# watch_v1_test_Rev01.net
KiCad netlist of a schematic drawn in EAGLE
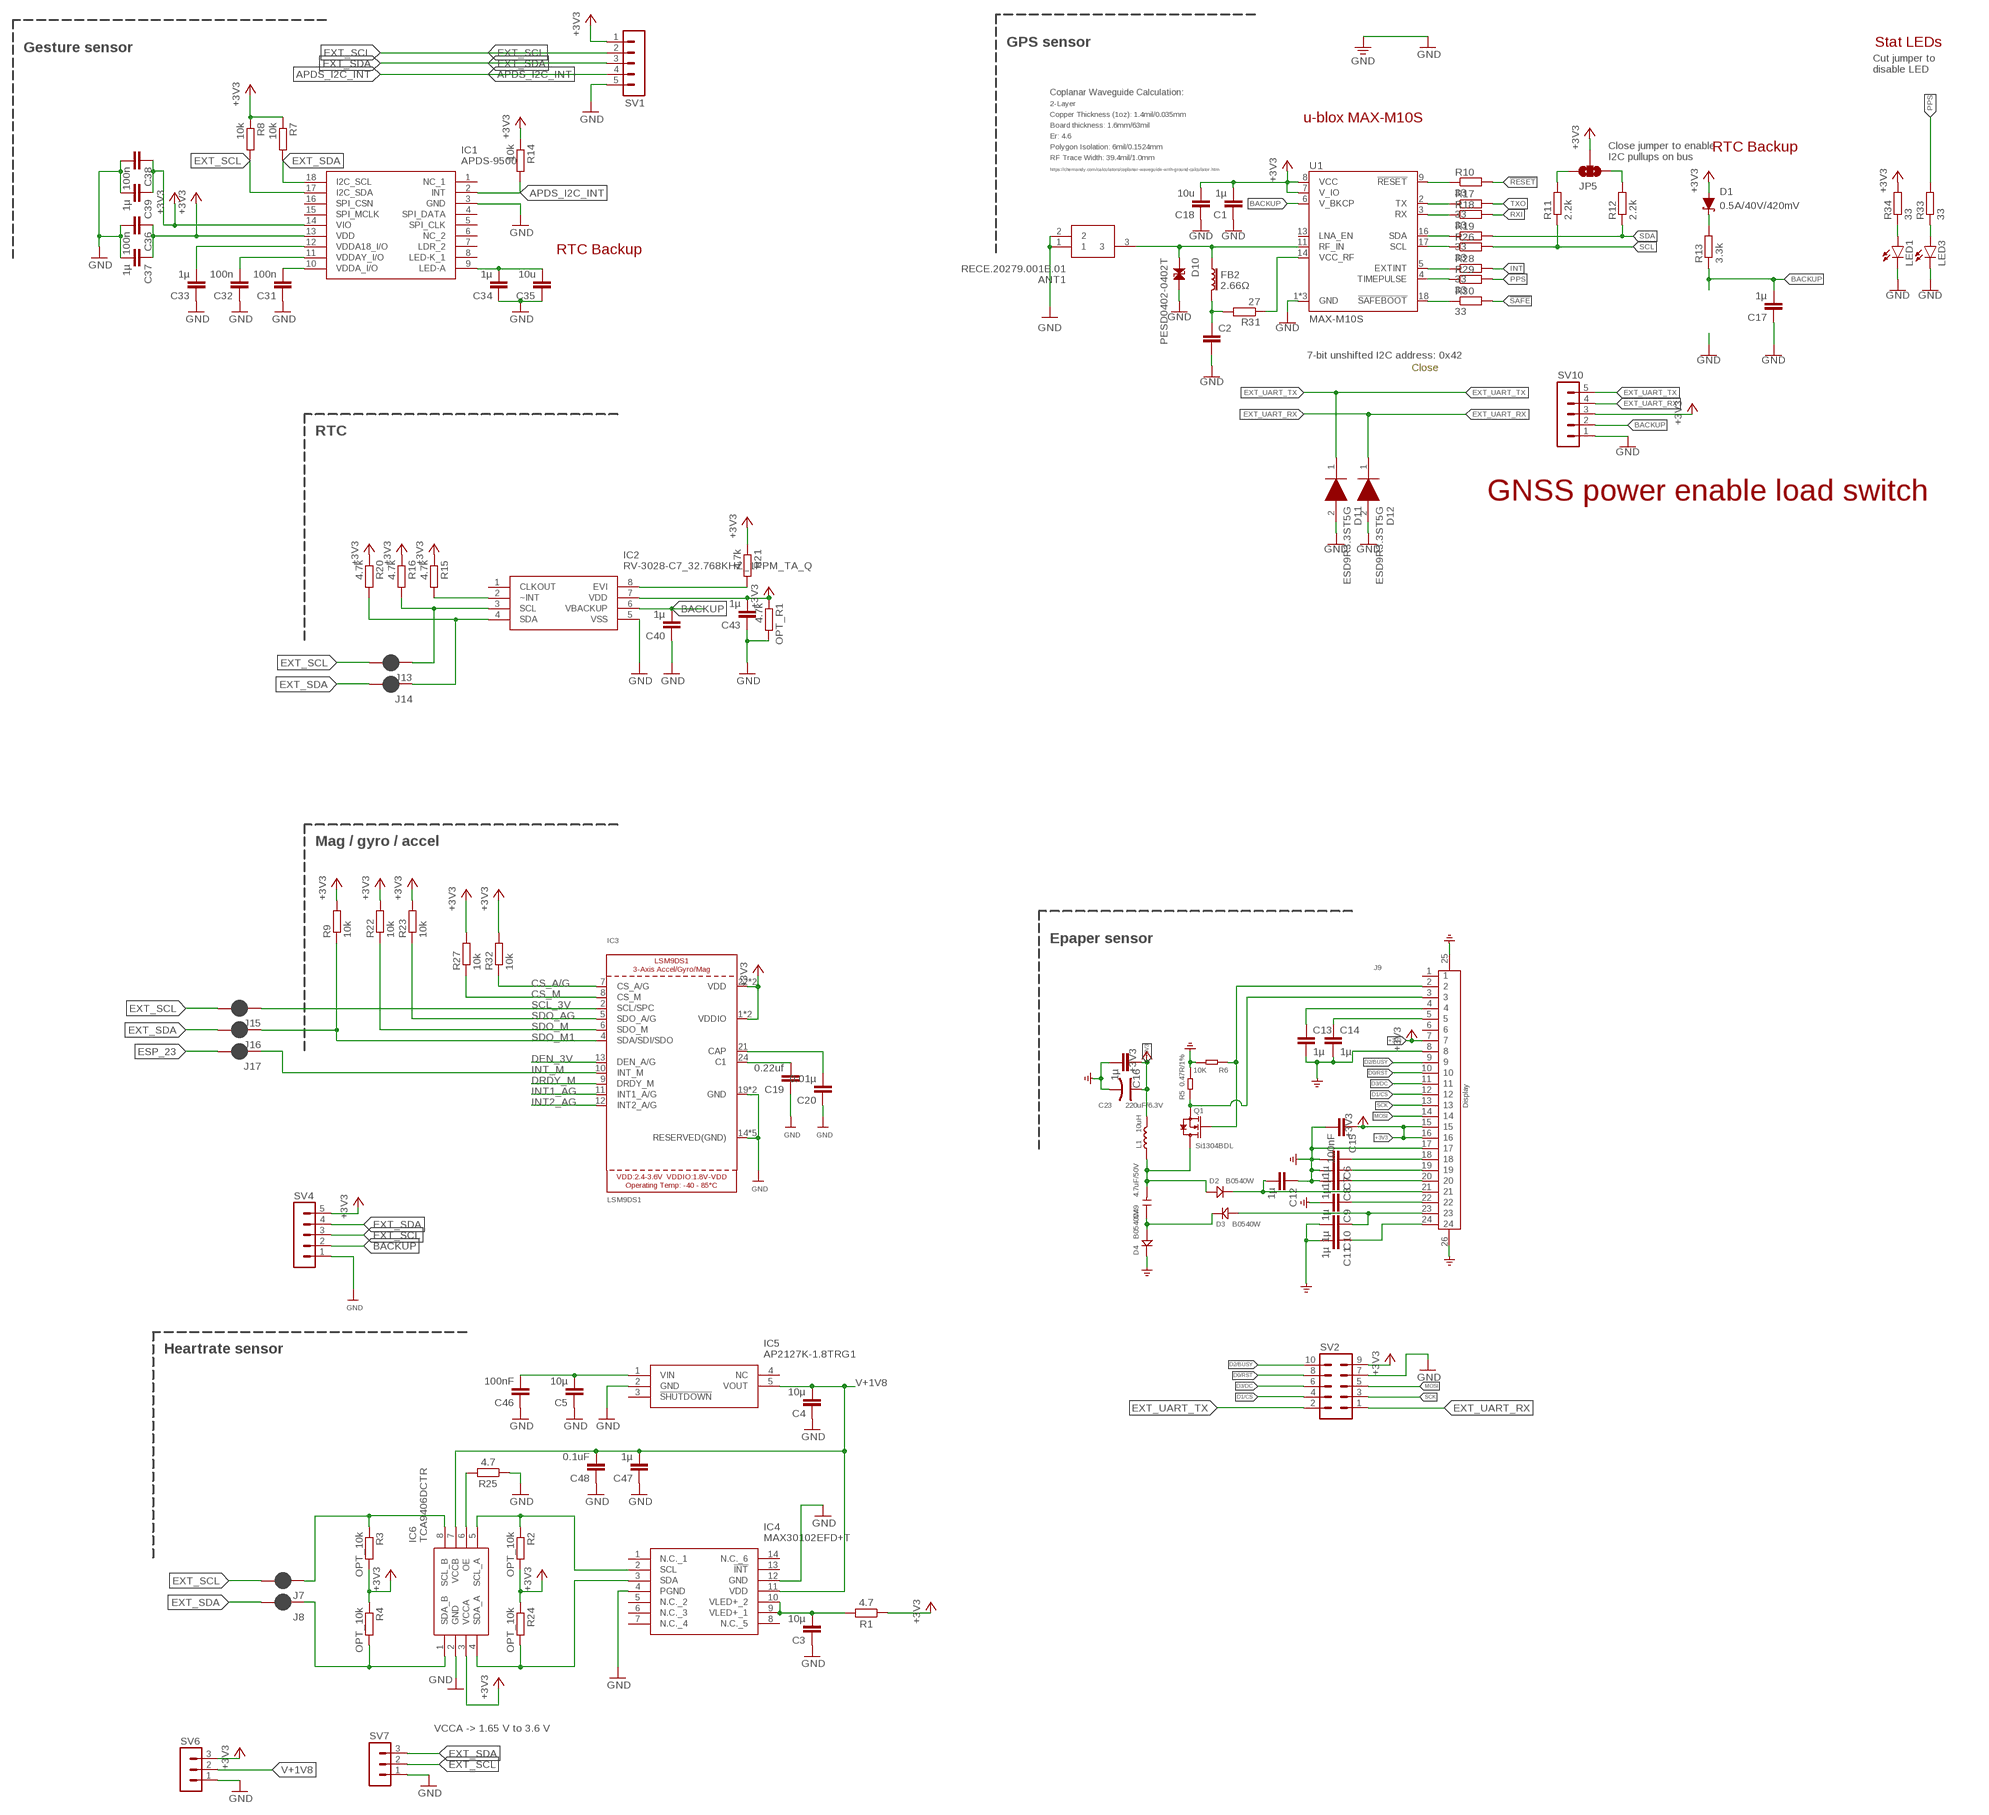
[diagram p0: schematic, sheet 1]

(export (version "E")
  (design (tool "Eeschema 10.0.6"))
  (components
    (comp (ref "ANT1")
      (value "RECE.20279.001E.01")
      (footprint "eagle-import:RECE.20279.001E.01")
      (fields (field (name "MOUSER_PART_NUMBER") "960-RECE20279001E01"))
      (libsource (lib "eagle-import") (part "RECE.20279.001E.01"))
    )
    (comp (ref "C1")
      (value "1µ")
      (footprint "eagle-import:C0402_S")
      (libsource (lib "eagle-import") (part "C0402_S"))
    )
    (comp (ref "C2")
      (value "47pF")
      (footprint "eagle-import:0402-TIGHT")
      (libsource (lib "eagle-import") (part "47PF-0402_TIGHT-25V-5%-X7R"))
    )
    (comp (ref "C3")
      (value "10µ")
      (footprint "eagle-import:C0402_S")
      (libsource (lib "eagle-import") (part "C0402_S"))
    )
    (comp (ref "C4")
      (value "10µ")
      (footprint "eagle-import:C0402_S")
      (libsource (lib "eagle-import") (part "C0402_S"))
    )
    (comp (ref "C5")
      (value "10µ")
      (footprint "eagle-import:C0402_S")
      (libsource (lib "eagle-import") (part "C0402_S"))
    )
    (comp (ref "C6")
      (value "1µ")
      (footprint "eagle-import:C0402_S")
      (libsource (lib "eagle-import") (part "C0402_S"))
    )
    (comp (ref "C7")
      (value "1µ")
      (footprint "eagle-import:C0402_S")
      (libsource (lib "eagle-import") (part "C0402_S"))
    )
    (comp (ref "C8")
      (value "1µ")
      (footprint "eagle-import:C0402_S")
      (libsource (lib "eagle-import") (part "C0402_S"))
    )
    (comp (ref "C9")
      (value "1µ")
      (footprint "eagle-import:C0402_S")
      (libsource (lib "eagle-import") (part "C0402_S"))
    )
    (comp (ref "C10")
      (value "1µ")
      (footprint "eagle-import:C0402_S")
      (libsource (lib "eagle-import") (part "C0402_S"))
    )
    (comp (ref "C11")
      (value "1µ")
      (footprint "eagle-import:C0402_S")
      (libsource (lib "eagle-import") (part "C0402_S"))
    )
    (comp (ref "C12")
      (value "1µ")
      (footprint "eagle-import:C0402_S")
      (libsource (lib "eagle-import") (part "C0402_S"))
    )
    (comp (ref "C13")
      (value "1µ")
      (footprint "eagle-import:C0402_S")
      (libsource (lib "eagle-import") (part "C0402_S"))
    )
    (comp (ref "C14")
      (value "1µ")
      (footprint "eagle-import:C0402_S")
      (libsource (lib "eagle-import") (part "C0402_S"))
    )
    (comp (ref "C15")
      (value "100nF")
      (footprint "eagle-import:C0402_S")
      (libsource (lib "eagle-import") (part "C0402_S"))
    )
    (comp (ref "C16")
      (value "1µ")
      (footprint "eagle-import:C0402_S")
      (libsource (lib "eagle-import") (part "C0402_S"))
    )
    (comp (ref "C17")
      (value "1µ")
      (footprint "eagle-import:C0402_S")
      (libsource (lib "eagle-import") (part "C0402_S"))
    )
    (comp (ref "C18")
      (value "10u")
      (footprint "eagle-import:C0402_S")
      (libsource (lib "eagle-import") (part "C0402_S"))
    )
    (comp (ref "C19")
      (value "0.22uf")
      (footprint "eagle-import:C0402_S")
      (libsource (lib "eagle-import") (part "C0402_S"))
    )
    (comp (ref "C20")
      (value "0.01µ")
      (footprint "eagle-import:C0402_S")
      (libsource (lib "eagle-import") (part "C0402_S"))
    )
    (comp (ref "C23")
      (value "220uF/6.3V")
      (footprint "eagle-import:AVX-B")
      (libsource (lib "eagle-import") (part "CAP-POLAR-AVX-B"))
    )
    (comp (ref "C31")
      (value "100n")
      (footprint "eagle-import:C0402_S")
      (libsource (lib "eagle-import") (part "C0402_S"))
    )
    (comp (ref "C32")
      (value "100n")
      (footprint "eagle-import:C0402_S")
      (libsource (lib "eagle-import") (part "C0402_S"))
    )
    (comp (ref "C33")
      (value "1µ")
      (footprint "eagle-import:C0402_S")
      (libsource (lib "eagle-import") (part "C0402_S"))
    )
    (comp (ref "C34")
      (value "1µ")
      (footprint "eagle-import:C0402_S")
      (libsource (lib "eagle-import") (part "C0402_S"))
    )
    (comp (ref "C35")
      (value "10u")
      (footprint "eagle-import:C0402_S")
      (libsource (lib "eagle-import") (part "C0402_S"))
    )
    (comp (ref "C36")
      (value "100n")
      (footprint "eagle-import:C0402_S")
      (libsource (lib "eagle-import") (part "C0402_S"))
    )
    (comp (ref "C37")
      (value "1µ")
      (footprint "eagle-import:C0402_S")
      (libsource (lib "eagle-import") (part "C0402_S"))
    )
    (comp (ref "C38")
      (value "100n")
      (footprint "eagle-import:C0402_S")
      (libsource (lib "eagle-import") (part "C0402_S"))
    )
    (comp (ref "C39")
      (value "1µ")
      (footprint "eagle-import:C0402_S")
      (libsource (lib "eagle-import") (part "C0402_S"))
    )
    (comp (ref "C40")
      (value "1µ")
      (footprint "eagle-import:C0402_S")
      (libsource (lib "eagle-import") (part "C0402_S"))
    )
    (comp (ref "C43")
      (value "1µ")
      (footprint "eagle-import:C0402_S")
      (libsource (lib "eagle-import") (part "C0402_S"))
    )
    (comp (ref "C46")
      (value "100nF")
      (footprint "eagle-import:C0402_S")
      (libsource (lib "eagle-import") (part "C0402_S"))
    )
    (comp (ref "C47")
      (value "1µ")
      (footprint "eagle-import:C0402_S")
      (libsource (lib "eagle-import") (part "C0402_S"))
    )
    (comp (ref "C48")
      (value "0.1uF")
      (footprint "eagle-import:C0402_S")
      (libsource (lib "eagle-import") (part "C0402_S"))
    )
    (comp (ref "C49")
      (value "4.7uF/50V")
      (footprint "eagle-import:C1206")
      (libsource (lib "eagle-import") (part "CAP-1206"))
    )
    (comp (ref "D1")
      (value "0.5A/40V/420mV")
      (footprint "eagle-import:SOD-323")
      (libsource (lib "eagle-import") (part "DIODE-SCHOTTKY-PMEG4005EJ"))
    )
    (comp (ref "D2")
      (value "B0540W")
      (footprint "eagle-import:SOD-323")
      (libsource (lib "eagle-import") (part "DIODE'0805'"))
    )
    (comp (ref "D3")
      (value "B0540W")
      (footprint "eagle-import:SOD-323")
      (libsource (lib "eagle-import") (part "DIODE'0805'"))
    )
    (comp (ref "D4")
      (value "B0540W")
      (footprint "eagle-import:SOD-323")
      (libsource (lib "eagle-import") (part "DIODE'0805'"))
    )
    (comp (ref "D10")
      (value "PESD0402-0402T")
      (footprint "eagle-import:0402-TIGHT")
      (libsource (lib "eagle-import") (part "PESD0402-0402T"))
    )
    (comp (ref "D11")
      (value "ESD9R3.3ST5G")
      (footprint "eagle-import:SODFL1006X40N")
      (fields (field (name "MOUSER_PART_NUMBER") "863-ESD9R3.3ST5G"))
      (libsource (lib "eagle-import") (part "ESD9R3.3ST5G"))
    )
    (comp (ref "D12")
      (value "ESD9R3.3ST5G")
      (footprint "eagle-import:SODFL1006X40N")
      (fields (field (name "MOUSER_PART_NUMBER") "863-ESD9R3.3ST5G"))
      (libsource (lib "eagle-import") (part "ESD9R3.3ST5G"))
    )
    (comp (ref "FB2")
      (value "2.66Ω")
      (footprint "eagle-import:0402-TIGHT")
      (libsource (lib "eagle-import") (part "FERRITE_BEAD-0402-2.66Ω-1GHZ"))
    )
    (comp (ref "IC1")
      (value "APDS-9500")
      (footprint "eagle-import:APDS9500")
      (fields (field (name "MOUSER_PART_NUMBER") "630-APDS-9500"))
      (libsource (lib "eagle-import") (part "APDS-9500"))
    )
    (comp (ref "IC2")
      (value "RV-3028-C7_32.768KHZ_1PPM_TA_Q")
      (footprint "eagle-import:RV3028C732768KHZ1PPMTAQC")
      (fields
        (field (name "MANUFACTURER_PART_NUMBER") "RV-3028-C7 32.768kHz 1ppm TA QC")
        (field (name "MOUSER_PART_NUMBER") "428-203591-MG01")
      )
      (libsource (lib "eagle-import") (part "RV-3028-C7_32.768KHZ_1PPM_TA_Q"))
    )
    (comp (ref "IC3")
      (value "LSM9DS1")
      (footprint "eagle-import:LGA24_3.5X3.1MM")
      (libsource (lib "eagle-import") (part "LSM9DS1"))
    )
    (comp (ref "IC4")
      (value "MAX30102EFD+T")
      (footprint "eagle-import:MAX30102EFDT")
      (fields (field (name "MOUSER_PART_NUMBER") "700-MAX30102EFD+T"))
      (libsource (lib "eagle-import") (part "MAX30102EFD+T"))
    )
    (comp (ref "IC5")
      (value "AP2127K-1.8TRG1")
      (footprint "eagle-import:SOT95P282X145-5N")
      (fields (field (name "MOUSER_PART_NUMBER") "621-AP2127K-1.8TRG1"))
      (libsource (lib "eagle-import") (part "AP2127K-1.8TRG1"))
    )
    (comp (ref "IC6")
      (value "TCA9406DCTR")
      (footprint "eagle-import:SOP65P400X130-8N")
      (fields (field (name "MOUSER_PART_NUMBER") "595-TCA9406DCTR"))
      (libsource (lib "eagle-import") (part "TCA9406DCTR"))
    )
    (comp (ref "J7")
      (value "SMT_JUMPER_2_NC_PASTE")
      (footprint "eagle-import:JUMPER_SMALL")
      (libsource (lib "eagle-import") (part "SMT_JUMPER_2_NC_PASTE"))
    )
    (comp (ref "J8")
      (value "SMT_JUMPER_2_NC_PASTE")
      (footprint "eagle-import:JUMPER_SMALL")
      (libsource (lib "eagle-import") (part "SMT_JUMPER_2_NC_PASTE"))
    )
    (comp (ref "J9")
      (value "Display")
      (footprint "eagle-import:FPCB24-SMD-0.5-17.6X5.0X2MM")
      (libsource (lib "eagle-import") (part "FPC-CONNECTOR-24P"))
    )
    (comp (ref "J13")
      (value "SMT_JUMPER_2_NC_PASTE")
      (footprint "eagle-import:JUMPER_SMALL")
      (libsource (lib "eagle-import") (part "SMT_JUMPER_2_NC_PASTE"))
    )
    (comp (ref "J14")
      (value "SMT_JUMPER_2_NC_PASTE")
      (footprint "eagle-import:JUMPER_SMALL")
      (libsource (lib "eagle-import") (part "SMT_JUMPER_2_NC_PASTE"))
    )
    (comp (ref "J15")
      (value "SMT_JUMPER_2_NC_PASTE")
      (footprint "eagle-import:JUMPER_SMALL")
      (libsource (lib "eagle-import") (part "SMT_JUMPER_2_NC_PASTE"))
    )
    (comp (ref "J16")
      (value "SMT_JUMPER_2_NC_PASTE")
      (footprint "eagle-import:JUMPER_SMALL")
      (libsource (lib "eagle-import") (part "SMT_JUMPER_2_NC_PASTE"))
    )
    (comp (ref "J17")
      (value "SMT_JUMPER_2_NC_PASTE")
      (footprint "eagle-import:JUMPER_SMALL")
      (libsource (lib "eagle-import") (part "SMT_JUMPER_2_NC_PASTE"))
    )
    (comp (ref "JP5")
      (value "JUMPER-SMT_3_NO_SILK")
      (footprint "eagle-import:SMT-JUMPER_3_NO_SILK")
      (libsource (lib "eagle-import") (part "JUMPER-SMT_3_NO_SILK"))
    )
    (comp (ref "L1")
      (value "10uH")
      (footprint "eagle-import:L0420")
      (libsource (lib "eagle-import") (part "INDUCTOR-SPD3D16-4R7M"))
    )
    (comp (ref "LED1")
      (value "LEDSML0603")
      (footprint "eagle-import:SML0603")
      (fields (field (name "MANUFACTURER") "Wurth Elektronik") (field (name "MPN") "150060GS84000"))
      (libsource (lib "eagle-import") (part "LEDSML0603"))
    )
    (comp (ref "LED3")
      (value "LEDSML0603")
      (footprint "eagle-import:SML0603")
      (fields (field (name "MANUFACTURER") "Wurth Elektronik") (field (name "MPN") "150060GS84000"))
      (libsource (lib "eagle-import") (part "LEDSML0603"))
    )
    (comp (ref "OPT_R1")
      (value "4.7k")
      (footprint "eagle-import:R0402")
      (libsource (lib "eagle-import") (part "R0402"))
    )
    (comp (ref "Q1")
      (value "Si1304BDL")
      (footprint "eagle-import:SOT-323")
      (libsource (lib "eagle-import") (part "MOSFET-N'SI1304BDL'"))
    )
    (comp (ref "R1")
      (value "4.7")
      (footprint "eagle-import:RESC1608X60")
      (libsource (lib "eagle-import") (part "RCHIP-0603(1608-METRIC)_"))
    )
    (comp (ref "R2")
      (value "OPT_10k")
      (footprint "eagle-import:R0402")
      (libsource (lib "eagle-import") (part "R0402"))
    )
    (comp (ref "R3")
      (value "OPT_10k")
      (footprint "eagle-import:R0402")
      (libsource (lib "eagle-import") (part "R0402"))
    )
    (comp (ref "R4")
      (value "OPT_10k")
      (footprint "eagle-import:R0402")
      (libsource (lib "eagle-import") (part "R0402"))
    )
    (comp (ref "R5")
      (value "0.47R/1%")
      (footprint "eagle-import:R0603")
      (libsource (lib "eagle-import") (part "RES-0603"))
    )
    (comp (ref "R6")
      (value "10K")
      (footprint "eagle-import:R0603")
      (libsource (lib "eagle-import") (part "RES-0603"))
    )
    (comp (ref "R7")
      (value "10k")
      (footprint "eagle-import:R0402")
      (libsource (lib "eagle-import") (part "R0402"))
    )
    (comp (ref "R8")
      (value "10k")
      (footprint "eagle-import:R0402")
      (libsource (lib "eagle-import") (part "R0402"))
    )
    (comp (ref "R9")
      (value "10k")
      (footprint "eagle-import:R0402")
      (libsource (lib "eagle-import") (part "R0402"))
    )
    (comp (ref "R10")
      (value "33")
      (footprint "eagle-import:R0402")
      (libsource (lib "eagle-import") (part "R0402"))
    )
    (comp (ref "R11")
      (value "2.2k")
      (footprint "eagle-import:R0402")
      (libsource (lib "eagle-import") (part "R0402"))
    )
    (comp (ref "R12")
      (value "2.2k")
      (footprint "eagle-import:R0402")
      (libsource (lib "eagle-import") (part "R0402"))
    )
    (comp (ref "R13")
      (value "3.3k")
      (footprint "eagle-import:R0402")
      (libsource (lib "eagle-import") (part "R0402"))
    )
    (comp (ref "R14")
      (value "10k")
      (footprint "eagle-import:R0402")
      (libsource (lib "eagle-import") (part "R0402"))
    )
    (comp (ref "R15")
      (value "4.7k")
      (footprint "eagle-import:R0402")
      (libsource (lib "eagle-import") (part "R0402"))
    )
    (comp (ref "R16")
      (value "4.7k")
      (footprint "eagle-import:R0402")
      (libsource (lib "eagle-import") (part "R0402"))
    )
    (comp (ref "R17")
      (value "33")
      (footprint "eagle-import:R0402")
      (libsource (lib "eagle-import") (part "R0402"))
    )
    (comp (ref "R18")
      (value "33")
      (footprint "eagle-import:R0402")
      (libsource (lib "eagle-import") (part "R0402"))
    )
    (comp (ref "R19")
      (value "33")
      (footprint "eagle-import:R0402")
      (libsource (lib "eagle-import") (part "R0402"))
    )
    (comp (ref "R20")
      (value "4.7k")
      (footprint "eagle-import:R0402")
      (libsource (lib "eagle-import") (part "R0402"))
    )
    (comp (ref "R21")
      (value "4.7k")
      (footprint "eagle-import:R0402")
      (libsource (lib "eagle-import") (part "R0402"))
    )
    (comp (ref "R22")
      (value "10k")
      (footprint "eagle-import:R0402")
      (libsource (lib "eagle-import") (part "R0402"))
    )
    (comp (ref "R23")
      (value "10k")
      (footprint "eagle-import:R0402")
      (libsource (lib "eagle-import") (part "R0402"))
    )
    (comp (ref "R24")
      (value "OPT_10k")
      (footprint "eagle-import:R0402")
      (libsource (lib "eagle-import") (part "R0402"))
    )
    (comp (ref "R25")
      (value "4.7")
      (footprint "eagle-import:RESC1608X60")
      (libsource (lib "eagle-import") (part "RCHIP-0603(1608-METRIC)_"))
    )
    (comp (ref "R26")
      (value "33")
      (footprint "eagle-import:R0402")
      (libsource (lib "eagle-import") (part "R0402"))
    )
    (comp (ref "R27")
      (value "10k")
      (footprint "eagle-import:R0402")
      (libsource (lib "eagle-import") (part "R0402"))
    )
    (comp (ref "R28")
      (value "33")
      (footprint "eagle-import:R0402")
      (libsource (lib "eagle-import") (part "R0402"))
    )
    (comp (ref "R29")
      (value "33")
      (footprint "eagle-import:R0402")
      (libsource (lib "eagle-import") (part "R0402"))
    )
    (comp (ref "R30")
      (value "33")
      (footprint "eagle-import:R0402")
      (libsource (lib "eagle-import") (part "R0402"))
    )
    (comp (ref "R31")
      (value "27")
      (footprint "eagle-import:R0402")
      (libsource (lib "eagle-import") (part "R0402"))
    )
    (comp (ref "R32")
      (value "10k")
      (footprint "eagle-import:R0402")
      (libsource (lib "eagle-import") (part "R0402"))
    )
    (comp (ref "R33")
      (value "33")
      (footprint "eagle-import:R0402")
      (libsource (lib "eagle-import") (part "R0402"))
    )
    (comp (ref "R34")
      (value "33")
      (footprint "eagle-import:R0402")
      (libsource (lib "eagle-import") (part "R0402"))
    )
    (comp (ref "SV1")
      (value "MA05-1")
      (footprint "eagle-import:MA05-1")
      (libsource (lib "eagle-import") (part "MA05-1"))
    )
    (comp (ref "SV2")
      (value "MA05-2")
      (footprint "eagle-import:MA05-2")
      (libsource (lib "eagle-import") (part "MA05-2"))
    )
    (comp (ref "SV4")
      (value "MA05-1")
      (footprint "eagle-import:MA05-1")
      (libsource (lib "eagle-import") (part "MA05-1"))
    )
    (comp (ref "SV6")
      (value "MA03-1")
      (footprint "eagle-import:MA03-1")
      (libsource (lib "eagle-import") (part "MA03-1"))
    )
    (comp (ref "SV7")
      (value "MA03-1")
      (footprint "eagle-import:MA03-1")
      (libsource (lib "eagle-import") (part "MA03-1"))
    )
    (comp (ref "SV10")
      (value "MA05-1")
      (footprint "eagle-import:MA05-1")
      (libsource (lib "eagle-import") (part "MA05-1"))
    )
    (comp (ref "U1")
      (value "MAX-M10S")
      (footprint "eagle-import:MAX-M10S")
      (libsource (lib "eagle-import") (part "MAX-M10S"))
    )
  )
  (nets
    (net (code "1") (name "+3V3") (class "Default")
      (node (ref "C1") (pin "P$2") (pinfunction "2_P$2") (pintype "passive"))
      (node (ref "C15") (pin "P$1") (pinfunction "1_P$1") (pintype "passive"))
      (node (ref "C16") (pin "P$1") (pinfunction "1_P$1") (pintype "passive"))
      (node (ref "C18") (pin "P$2") (pinfunction "2_P$2") (pintype "passive"))
      (node (ref "C23") (pin "+") (pinfunction "+_+") (pintype "passive"))
      (node (ref "C36") (pin "P$1") (pinfunction "1_P$1") (pintype "passive"))
      (node (ref "C37") (pin "P$1") (pinfunction "1_P$1") (pintype "passive"))
      (node (ref "C38") (pin "P$1") (pinfunction "1_P$1") (pintype "passive"))
      (node (ref "C39") (pin "P$1") (pinfunction "1_P$1") (pintype "passive"))
      (node (ref "C43") (pin "P$2") (pinfunction "2_P$2") (pintype "passive"))
      (node (ref "D1") (pin "A") (pinfunction "A_A") (pintype "passive"))
      (node (ref "IC1") (pin "13") (pinfunction "VDD_13") (pintype "bidirectional"))
      (node (ref "IC1") (pin "14") (pinfunction "VIO_14") (pintype "bidirectional"))
      (node (ref "IC2") (pin "7") (pinfunction "VDD_7") (pintype "bidirectional"))
      (node (ref "IC3") (pin "1") (pinfunction "VDDIO_1") (pintype "power_in"))
      (node (ref "IC3") (pin "22") (pinfunction "VDD_22") (pintype "power_in"))
      (node (ref "IC3") (pin "23") (pinfunction "VDD_23") (pintype "power_in"))
      (node (ref "IC3") (pin "3") (pinfunction "VDDIO_3") (pintype "power_in"))
      (node (ref "IC6") (pin "3") (pinfunction "VCCA_3") (pintype "bidirectional"))
      (node (ref "J9") (pin "15") (pinfunction "15_15") (pintype "bidirectional"))
      (node (ref "J9") (pin "16") (pinfunction "16_16") (pintype "bidirectional"))
      (node (ref "J9") (pin "7") (pinfunction "7_7") (pintype "bidirectional"))
      (node (ref "JP5") (pin "2") (pinfunction "2_2") (pintype "passive"))
      (node (ref "L1") (pin "2") (pinfunction "2_2") (pintype "passive"))
      (node (ref "OPT_R1") (pin "1") (pinfunction "1_1") (pintype "passive"))
      (node (ref "R1") (pin "1") (pinfunction "1_1") (pintype "passive"))
      (node (ref "R14") (pin "1") (pinfunction "1_1") (pintype "passive"))
      (node (ref "R15") (pin "1") (pinfunction "1_1") (pintype "passive"))
      (node (ref "R16") (pin "1") (pinfunction "1_1") (pintype "passive"))
      (node (ref "R2") (pin "2") (pinfunction "2_2") (pintype "passive"))
      (node (ref "R20") (pin "1") (pinfunction "1_1") (pintype "passive"))
      (node (ref "R21") (pin "1") (pinfunction "1_1") (pintype "passive"))
      (node (ref "R22") (pin "2") (pinfunction "2_2") (pintype "passive"))
      (node (ref "R23") (pin "2") (pinfunction "2_2") (pintype "passive"))
      (node (ref "R24") (pin "1") (pinfunction "1_1") (pintype "passive"))
      (node (ref "R27") (pin "2") (pinfunction "2_2") (pintype "passive"))
      (node (ref "R3") (pin "2") (pinfunction "2_2") (pintype "passive"))
      (node (ref "R32") (pin "2") (pinfunction "2_2") (pintype "passive"))
      (node (ref "R34") (pin "2") (pinfunction "2_2") (pintype "passive"))
      (node (ref "R4") (pin "1") (pinfunction "1_1") (pintype "passive"))
      (node (ref "R7") (pin "1") (pinfunction "1_1") (pintype "passive"))
      (node (ref "R8") (pin "1") (pinfunction "1_1") (pintype "passive"))
      (node (ref "R9") (pin "2") (pinfunction "2_2") (pintype "passive"))
      (node (ref "SV1") (pin "1") (pinfunction "1_1") (pintype "passive"))
      (node (ref "SV10") (pin "3") (pinfunction "3_3") (pintype "passive"))
      (node (ref "SV2") (pin "9") (pinfunction "9_9") (pintype "passive"))
      (node (ref "SV4") (pin "5") (pinfunction "5_5") (pintype "passive"))
      (node (ref "SV6") (pin "3") (pinfunction "3_3") (pintype "passive"))
      (node (ref "U1") (pin "7") (pinfunction "V_IO_7") (pintype "bidirectional"))
      (node (ref "U1") (pin "8") (pinfunction "VCC_8") (pintype "bidirectional"))
    )
    (net (code "2") (name "/CS_A{slash}G") (class "Default")
      (node (ref "IC3") (pin "7") (pinfunction "CS_A/G_7") (pintype "bidirectional"))
      (node (ref "R32") (pin "1") (pinfunction "1_1") (pintype "passive"))
    )
    (net (code "3") (name "/CS_M") (class "Default")
      (node (ref "IC3") (pin "8") (pinfunction "CS_M_8") (pintype "bidirectional"))
      (node (ref "R27") (pin "1") (pinfunction "1_1") (pintype "passive"))
    )
    (net (code "4") (name "/DEN_3V") (class "Default")
      (node (ref "IC3") (pin "13") (pinfunction "DEN_A/G_13") (pintype "bidirectional"))
    )
    (net (code "5") (name "/DRDY_M") (class "Default")
      (node (ref "IC3") (pin "9") (pinfunction "DRDY_M_9") (pintype "bidirectional"))
    )
    (net (code "6") (name "/INT1_AG") (class "Default")
      (node (ref "IC3") (pin "11") (pinfunction "INT1_A/G_11") (pintype "bidirectional"))
    )
    (net (code "7") (name "/INT2_AG") (class "Default")
      (node (ref "IC3") (pin "12") (pinfunction "INT2_A/G_12") (pintype "bidirectional"))
    )
    (net (code "8") (name "/INT_M") (class "Default")
      (node (ref "IC3") (pin "10") (pinfunction "INT_M_10") (pintype "bidirectional"))
      (node (ref "J17") (pin "P$1") (pinfunction "1_P$1") (pintype "passive"))
    )
    (net (code "9") (name "/SCL_3V") (class "Default")
      (node (ref "IC3") (pin "2") (pinfunction "SCL/SPC_2") (pintype "bidirectional"))
      (node (ref "J15") (pin "P$1") (pinfunction "1_P$1") (pintype "passive"))
    )
    (net (code "10") (name "/SDO_AG") (class "Default")
      (node (ref "IC3") (pin "5") (pinfunction "SDO_A/G_5") (pintype "bidirectional"))
      (node (ref "R23") (pin "1") (pinfunction "1_1") (pintype "passive"))
    )
    (net (code "11") (name "/SDO_M") (class "Default")
      (node (ref "IC3") (pin "6") (pinfunction "SDO_M_6") (pintype "bidirectional"))
      (node (ref "R22") (pin "1") (pinfunction "1_1") (pintype "passive"))
    )
    (net (code "12") (name "/SDO_M1") (class "Default")
      (node (ref "IC3") (pin "4") (pinfunction "SDA/SDI/SDO_4") (pintype "bidirectional"))
      (node (ref "J16") (pin "P$1") (pinfunction "1_P$1") (pintype "passive"))
      (node (ref "R9") (pin "1") (pinfunction "1_1") (pintype "passive"))
    )
    (net (code "13") (name "/~{RESET}") (class "Default")
      (node (ref "R10") (pin "2") (pinfunction "2_2") (pintype "passive"))
    )
    (net (code "14") (name "/~{SAFE}") (class "Default")
      (node (ref "R30") (pin "2") (pinfunction "2_2") (pintype "passive"))
    )
    (net (code "15") (name "APDS_I2C_INT") (class "Default")
      (node (ref "IC1") (pin "2") (pinfunction "INT_2") (pintype "bidirectional"))
      (node (ref "R14") (pin "2") (pinfunction "2_2") (pintype "passive"))
      (node (ref "SV1") (pin "4") (pinfunction "4_4") (pintype "passive"))
    )
    (net (code "16") (name "BACKUP") (class "Default")
      (node (ref "C17") (pin "P$2") (pinfunction "2_P$2") (pintype "passive"))
      (node (ref "C40") (pin "P$2") (pinfunction "2_P$2") (pintype "passive"))
      (node (ref "IC2") (pin "6") (pinfunction "VBACKUP_6") (pintype "bidirectional"))
      (node (ref "R13") (pin "1") (pinfunction "1_1") (pintype "passive"))
      (node (ref "SV10") (pin "2") (pinfunction "2_2") (pintype "passive"))
      (node (ref "SV4") (pin "2") (pinfunction "2_2") (pintype "passive"))
      (node (ref "U1") (pin "6") (pinfunction "V_BKCP_6") (pintype "bidirectional"))
    )
    (net (code "17") (name "D0{slash}RST") (class "Default")
      (node (ref "J9") (pin "10") (pinfunction "10_10") (pintype "bidirectional"))
      (node (ref "SV2") (pin "8") (pinfunction "8_8") (pintype "passive"))
    )
    (net (code "18") (name "D1{slash}CS") (class "Default")
      (node (ref "J9") (pin "12") (pinfunction "12_12") (pintype "bidirectional"))
      (node (ref "SV2") (pin "4") (pinfunction "4_4") (pintype "passive"))
    )
    (net (code "19") (name "D2{slash}BUSY") (class "Default")
      (node (ref "J9") (pin "9") (pinfunction "9_9") (pintype "bidirectional"))
      (node (ref "SV2") (pin "10") (pinfunction "10_10") (pintype "passive"))
    )
    (net (code "20") (name "D3{slash}DC") (class "Default")
      (node (ref "J9") (pin "11") (pinfunction "11_11") (pintype "bidirectional"))
      (node (ref "SV2") (pin "6") (pinfunction "6_6") (pintype "passive"))
    )
    (net (code "21") (name "ESP_23") (class "Default")
      (node (ref "J17") (pin "P$2") (pinfunction "2_P$2") (pintype "passive"))
    )
    (net (code "22") (name "EXT_SCL") (class "Default")
      (node (ref "IC1") (pin "17") (pinfunction "I2C_SDA_17") (pintype "bidirectional"))
      (node (ref "J13") (pin "P$2") (pinfunction "2_P$2") (pintype "passive"))
      (node (ref "J15") (pin "P$2") (pinfunction "2_P$2") (pintype "passive"))
      (node (ref "J7") (pin "P$2") (pinfunction "2_P$2") (pintype "passive"))
      (node (ref "R8") (pin "2") (pinfunction "2_2") (pintype "passive"))
      (node (ref "SV1") (pin "2") (pinfunction "2_2") (pintype "passive"))
      (node (ref "SV4") (pin "3") (pinfunction "3_3") (pintype "passive"))
      (node (ref "SV7") (pin "2") (pinfunction "2_2") (pintype "passive"))
    )
    (net (code "23") (name "EXT_SDA") (class "Default")
      (node (ref "IC1") (pin "18") (pinfunction "I2C_SCL_18") (pintype "bidirectional"))
      (node (ref "J14") (pin "P$2") (pinfunction "2_P$2") (pintype "passive"))
      (node (ref "J16") (pin "P$2") (pinfunction "2_P$2") (pintype "passive"))
      (node (ref "J8") (pin "P$2") (pinfunction "2_P$2") (pintype "passive"))
      (node (ref "R7") (pin "2") (pinfunction "2_2") (pintype "passive"))
      (node (ref "SV1") (pin "3") (pinfunction "3_3") (pintype "passive"))
      (node (ref "SV4") (pin "4") (pinfunction "4_4") (pintype "passive"))
      (node (ref "SV7") (pin "3") (pinfunction "3_3") (pintype "passive"))
    )
    (net (code "24") (name "EXT_UART_RX") (class "Default")
      (node (ref "D12") (pin "1") (pinfunction "K_1") (pintype "bidirectional"))
      (node (ref "SV10") (pin "4") (pinfunction "4_4") (pintype "passive"))
      (node (ref "SV2") (pin "1") (pinfunction "1_1") (pintype "passive"))
    )
    (net (code "25") (name "EXT_UART_TX") (class "Default")
      (node (ref "D11") (pin "1") (pinfunction "K_1") (pintype "bidirectional"))
      (node (ref "SV10") (pin "5") (pinfunction "5_5") (pintype "passive"))
      (node (ref "SV2") (pin "2") (pinfunction "2_2") (pintype "passive"))
    )
    (net (code "26") (name "GND") (class "Default")
      (node (ref "ANT1") (pin "1") (pinfunction "1_1") (pintype "bidirectional"))
      (node (ref "ANT1") (pin "2") (pinfunction "2_2") (pintype "bidirectional"))
      (node (ref "C1") (pin "P$1") (pinfunction "1_P$1") (pintype "passive"))
      (node (ref "C10") (pin "P$2") (pinfunction "2_P$2") (pintype "passive"))
      (node (ref "C11") (pin "P$2") (pinfunction "2_P$2") (pintype "passive"))
      (node (ref "C12") (pin "P$1") (pinfunction "1_P$1") (pintype "passive"))
      (node (ref "C13") (pin "P$2") (pinfunction "2_P$2") (pintype "passive"))
      (node (ref "C14") (pin "P$2") (pinfunction "2_P$2") (pintype "passive"))
      (node (ref "C15") (pin "P$2") (pinfunction "2_P$2") (pintype "passive"))
      (node (ref "C16") (pin "P$2") (pinfunction "2_P$2") (pintype "passive"))
      (node (ref "C17") (pin "P$1") (pinfunction "1_P$1") (pintype "passive"))
      (node (ref "C18") (pin "P$1") (pinfunction "1_P$1") (pintype "passive"))
      (node (ref "C19") (pin "P$1") (pinfunction "1_P$1") (pintype "passive"))
      (node (ref "C2") (pin "2") (pinfunction "2_2") (pintype "passive"))
      (node (ref "C20") (pin "P$1") (pinfunction "1_P$1") (pintype "passive"))
      (node (ref "C23") (pin "-") (pinfunction "-_-") (pintype "passive"))
      (node (ref "C3") (pin "P$1") (pinfunction "1_P$1") (pintype "passive"))
      (node (ref "C31") (pin "P$1") (pinfunction "1_P$1") (pintype "passive"))
      (node (ref "C32") (pin "P$1") (pinfunction "1_P$1") (pintype "passive"))
      (node (ref "C33") (pin "P$1") (pinfunction "1_P$1") (pintype "passive"))
      (node (ref "C34") (pin "P$1") (pinfunction "1_P$1") (pintype "passive"))
      (node (ref "C35") (pin "P$1") (pinfunction "1_P$1") (pintype "passive"))
      (node (ref "C36") (pin "P$2") (pinfunction "2_P$2") (pintype "passive"))
      (node (ref "C37") (pin "P$2") (pinfunction "2_P$2") (pintype "passive"))
      (node (ref "C38") (pin "P$2") (pinfunction "2_P$2") (pintype "passive"))
      (node (ref "C39") (pin "P$2") (pinfunction "2_P$2") (pintype "passive"))
      (node (ref "C4") (pin "P$1") (pinfunction "1_P$1") (pintype "passive"))
      (node (ref "C40") (pin "P$1") (pinfunction "1_P$1") (pintype "passive"))
      (node (ref "C43") (pin "P$1") (pinfunction "1_P$1") (pintype "passive"))
      (node (ref "C46") (pin "P$1") (pinfunction "1_P$1") (pintype "passive"))
      (node (ref "C47") (pin "P$1") (pinfunction "1_P$1") (pintype "passive"))
      (node (ref "C48") (pin "P$1") (pinfunction "1_P$1") (pintype "passive"))
      (node (ref "C5") (pin "P$1") (pinfunction "1_P$1") (pintype "passive"))
      (node (ref "C6") (pin "P$2") (pinfunction "2_P$2") (pintype "passive"))
      (node (ref "C7") (pin "P$2") (pinfunction "2_P$2") (pintype "passive"))
      (node (ref "C8") (pin "P$2") (pinfunction "2_P$2") (pintype "passive"))
      (node (ref "C9") (pin "P$2") (pinfunction "2_P$2") (pintype "passive"))
      (node (ref "D10") (pin "2") (pinfunction "2_2") (pintype "bidirectional"))
      (node (ref "D11") (pin "2") (pinfunction "A_2") (pintype "bidirectional"))
      (node (ref "D12") (pin "2") (pinfunction "A_2") (pintype "bidirectional"))
      (node (ref "D4") (pin "-") (pinfunction "-_-") (pintype "passive"))
      (node (ref "IC1") (pin "3") (pinfunction "GND_3") (pintype "bidirectional"))
      (node (ref "IC2") (pin "5") (pinfunction "VSS_5") (pintype "bidirectional"))
      (node (ref "IC3") (pin "14") (pinfunction "RESERVED(GND)_14") (pintype "power_in"))
      (node (ref "IC3") (pin "15") (pinfunction "RESERVED(GND)_15") (pintype "power_in"))
      (node (ref "IC3") (pin "16") (pinfunction "RESERVED(GND)_16") (pintype "power_in"))
      (node (ref "IC3") (pin "17") (pinfunction "RESERVED(GND)_17") (pintype "power_in"))
      (node (ref "IC3") (pin "18") (pinfunction "RESERVED(GND)_18") (pintype "power_in"))
      (node (ref "IC3") (pin "19") (pinfunction "GND_19") (pintype "power_in"))
      (node (ref "IC3") (pin "20") (pinfunction "GND_20") (pintype "power_in"))
      (node (ref "IC4") (pin "12") (pinfunction "GND_12") (pintype "bidirectional"))
      (node (ref "IC4") (pin "4") (pinfunction "PGND_4") (pintype "bidirectional"))
      (node (ref "IC5") (pin "2") (pinfunction "GND_2") (pintype "bidirectional"))
      (node (ref "IC6") (pin "2") (pinfunction "GND_2") (pintype "bidirectional"))
      (node (ref "J9") (pin "17") (pinfunction "17_17") (pintype "bidirectional"))
      (node (ref "J9") (pin "25") (pinfunction "P1_25") (pintype "bidirectional"))
      (node (ref "J9") (pin "26") (pinfunction "P2_26") (pintype "bidirectional"))
      (node (ref "J9") (pin "8") (pinfunction "8_8") (pintype "bidirectional"))
      (node (ref "LED1") (pin "C") (pinfunction "C_C") (pintype "passive"))
      (node (ref "LED3") (pin "C") (pinfunction "C_C") (pintype "passive"))
      (node (ref "OPT_R1") (pin "2") (pinfunction "2_2") (pintype "passive"))
      (node (ref "R25") (pin "1") (pinfunction "1_1") (pintype "passive"))
      (node (ref "R5") (pin "2") (pinfunction "2_2") (pintype "passive"))
      (node (ref "R6") (pin "2") (pinfunction "2_2") (pintype "passive"))
      (node (ref "SV1") (pin "5") (pinfunction "5_5") (pintype "passive"))
      (node (ref "SV10") (pin "1") (pinfunction "1_1") (pintype "passive"))
      (node (ref "SV2") (pin "7") (pinfunction "7_7") (pintype "passive"))
      (node (ref "SV4") (pin "1") (pinfunction "1_1") (pintype "passive"))
      (node (ref "SV6") (pin "1") (pinfunction "1_1") (pintype "passive"))
      (node (ref "SV7") (pin "1") (pinfunction "1_1") (pintype "passive"))
      (node (ref "U1") (pin "1") (pinfunction "GND_1") (pintype "bidirectional"))
      (node (ref "U1") (pin "10") (pinfunction "GND_10") (pintype "bidirectional"))
      (node (ref "U1") (pin "12") (pinfunction "GND_12") (pintype "bidirectional"))
    )
    (net (code "27") (name "INT") (class "Default")
      (node (ref "R28") (pin "2") (pinfunction "2_2") (pintype "passive"))
    )
    (net (code "28") (name "MOSI") (class "Default")
      (node (ref "J9") (pin "14") (pinfunction "14_14") (pintype "bidirectional"))
      (node (ref "SV2") (pin "5") (pinfunction "5_5") (pintype "passive"))
    )
    (net (code "29") (name "Net-(C2-Pad1)") (class "Default")
      (node (ref "C2") (pin "1") (pinfunction "1_1") (pintype "passive"))
      (node (ref "FB2") (pin "2") (pinfunction "2_2") (pintype "passive"))
      (node (ref "R31") (pin "2") (pinfunction "2_2") (pintype "passive"))
    )
    (net (code "30") (name "Net-(C3-2)") (class "Default")
      (node (ref "C3") (pin "P$2") (pinfunction "2_P$2") (pintype "passive"))
      (node (ref "IC4") (pin "10") (pinfunction "VLED+_2_10") (pintype "bidirectional"))
      (node (ref "IC4") (pin "9") (pinfunction "VLED+_1_9") (pintype "bidirectional"))
      (node (ref "R1") (pin "2") (pinfunction "2_2") (pintype "passive"))
    )
    (net (code "31") (name "Net-(C6-1)") (class "Default")
      (node (ref "C6") (pin "P$1") (pinfunction "1_P$1") (pintype "passive"))
      (node (ref "J9") (pin "18") (pinfunction "18_18") (pintype "bidirectional"))
    )
    (net (code "32") (name "Net-(C7-1)") (class "Default")
      (node (ref "C7") (pin "P$1") (pinfunction "1_P$1") (pintype "passive"))
      (node (ref "J9") (pin "19") (pinfunction "19_19") (pintype "bidirectional"))
    )
    (net (code "33") (name "Net-(C8-1)") (class "Default")
      (node (ref "C8") (pin "P$1") (pinfunction "1_P$1") (pintype "passive"))
      (node (ref "J9") (pin "20") (pinfunction "20_20") (pintype "bidirectional"))
    )
    (net (code "34") (name "Net-(C9-1)") (class "Default")
      (node (ref "C9") (pin "P$1") (pinfunction "1_P$1") (pintype "passive"))
      (node (ref "J9") (pin "22") (pinfunction "22_22") (pintype "bidirectional"))
    )
    (net (code "35") (name "Net-(C10-1)") (class "Default")
      (node (ref "C10") (pin "P$1") (pinfunction "1_P$1") (pintype "passive"))
      (node (ref "D3") (pin "+") (pinfunction "+_+") (pintype "passive"))
      (node (ref "J9") (pin "23") (pinfunction "23_23") (pintype "bidirectional"))
    )
    (net (code "36") (name "Net-(C11-1)") (class "Default")
      (node (ref "C11") (pin "P$1") (pinfunction "1_P$1") (pintype "passive"))
      (node (ref "J9") (pin "24") (pinfunction "24_24") (pintype "bidirectional"))
    )
    (net (code "37") (name "Net-(C12-2)") (class "Default")
      (node (ref "C12") (pin "P$2") (pinfunction "2_P$2") (pintype "passive"))
      (node (ref "D2") (pin "-") (pinfunction "-_-") (pintype "passive"))
      (node (ref "J9") (pin "21") (pinfunction "21_21") (pintype "bidirectional"))
    )
    (net (code "38") (name "Net-(C13-1)") (class "Default")
      (node (ref "C13") (pin "P$1") (pinfunction "1_P$1") (pintype "passive"))
      (node (ref "J9") (pin "4") (pinfunction "4_4") (pintype "bidirectional"))
    )
    (net (code "39") (name "Net-(C14-1)") (class "Default")
      (node (ref "C14") (pin "P$1") (pinfunction "1_P$1") (pintype "passive"))
      (node (ref "J9") (pin "5") (pinfunction "5_5") (pintype "bidirectional"))
    )
    (net (code "40") (name "Net-(C19-2)") (class "Default")
      (node (ref "C19") (pin "P$2") (pinfunction "2_P$2") (pintype "passive"))
      (node (ref "IC3") (pin "24") (pinfunction "C1_24") (pintype "bidirectional"))
    )
    (net (code "41") (name "Net-(C20-2)") (class "Default")
      (node (ref "C20") (pin "P$2") (pinfunction "2_P$2") (pintype "passive"))
      (node (ref "IC3") (pin "21") (pinfunction "CAP_21") (pintype "bidirectional"))
    )
    (net (code "42") (name "Net-(C31-2)") (class "Default")
      (node (ref "C31") (pin "P$2") (pinfunction "2_P$2") (pintype "passive"))
      (node (ref "IC1") (pin "10") (pinfunction "VDDA_I/O_10") (pintype "bidirectional"))
    )
    (net (code "43") (name "Net-(C32-2)") (class "Default")
      (node (ref "C32") (pin "P$2") (pinfunction "2_P$2") (pintype "passive"))
      (node (ref "IC1") (pin "11") (pinfunction "VDDAY_I/O_11") (pintype "bidirectional"))
    )
    (net (code "44") (name "Net-(C33-2)") (class "Default")
      (node (ref "C33") (pin "P$2") (pinfunction "2_P$2") (pintype "passive"))
      (node (ref "IC1") (pin "12") (pinfunction "VDDA18_I/O_12") (pintype "bidirectional"))
    )
    (net (code "45") (name "Net-(C34-2)") (class "Default")
      (node (ref "C34") (pin "P$2") (pinfunction "2_P$2") (pintype "passive"))
      (node (ref "C35") (pin "P$2") (pinfunction "2_P$2") (pintype "passive"))
      (node (ref "IC1") (pin "9") (pinfunction "LED-A_9") (pintype "bidirectional"))
    )
    (net (code "46") (name "Net-(C46-2)") (class "Default")
      (node (ref "C46") (pin "P$2") (pinfunction "2_P$2") (pintype "passive"))
      (node (ref "C5") (pin "P$2") (pinfunction "2_P$2") (pintype "passive"))
      (node (ref "IC5") (pin "1") (pinfunction "VIN_1") (pintype "bidirectional"))
    )
    (net (code "47") (name "Net-(C49-Pad1)") (class "Default")
      (node (ref "C49") (pin "1") (pinfunction "1_1") (pintype "passive"))
      (node (ref "D3") (pin "-") (pinfunction "-_-") (pintype "passive"))
      (node (ref "D4") (pin "+") (pinfunction "+_+") (pintype "passive"))
    )
    (net (code "48") (name "Net-(D1-PadC)") (class "Default")
      (node (ref "D1") (pin "C") (pinfunction "C_C") (pintype "passive"))
      (node (ref "R13") (pin "2") (pinfunction "2_2") (pintype "passive"))
    )
    (net (code "49") (name "Net-(IC2-EVI)") (class "Default")
      (node (ref "IC2") (pin "8") (pinfunction "EVI_8") (pintype "bidirectional"))
      (node (ref "R21") (pin "2") (pinfunction "2_2") (pintype "passive"))
    )
    (net (code "50") (name "Net-(IC2-SCL)") (class "Default")
      (node (ref "IC2") (pin "3") (pinfunction "SCL_3") (pintype "bidirectional"))
      (node (ref "J13") (pin "P$1") (pinfunction "1_P$1") (pintype "passive"))
      (node (ref "R16") (pin "2") (pinfunction "2_2") (pintype "passive"))
    )
    (net (code "51") (name "Net-(IC2-SDA)") (class "Default")
      (node (ref "IC2") (pin "4") (pinfunction "SDA_4") (pintype "bidirectional"))
      (node (ref "J14") (pin "P$1") (pinfunction "1_P$1") (pintype "passive"))
      (node (ref "R20") (pin "2") (pinfunction "2_2") (pintype "passive"))
    )
    (net (code "52") (name "Net-(IC2-~{INT})") (class "Default")
      (node (ref "IC2") (pin "2") (pinfunction "~{INT}_2") (pintype "bidirectional"))
      (node (ref "R15") (pin "2") (pinfunction "2_2") (pintype "passive"))
    )
    (net (code "53") (name "Net-(IC4-SCL)") (class "Default")
      (node (ref "IC4") (pin "2") (pinfunction "SCL_2") (pintype "bidirectional"))
      (node (ref "IC6") (pin "5") (pinfunction "SCL_A_5") (pintype "bidirectional"))
      (node (ref "R2") (pin "1") (pinfunction "1_1") (pintype "passive"))
    )
    (net (code "54") (name "Net-(IC4-SDA)") (class "Default")
      (node (ref "IC4") (pin "3") (pinfunction "SDA_3") (pintype "bidirectional"))
      (node (ref "IC6") (pin "4") (pinfunction "SDA_A_4") (pintype "bidirectional"))
      (node (ref "R24") (pin "2") (pinfunction "2_2") (pintype "passive"))
    )
    (net (code "55") (name "Net-(IC6-OE)") (class "Default")
      (node (ref "IC6") (pin "6") (pinfunction "OE_6") (pintype "bidirectional"))
      (node (ref "R25") (pin "2") (pinfunction "2_2") (pintype "passive"))
    )
    (net (code "56") (name "Net-(IC6-SCL_B)") (class "Default")
      (node (ref "IC6") (pin "8") (pinfunction "SCL_B_8") (pintype "bidirectional"))
      (node (ref "J7") (pin "P$1") (pinfunction "1_P$1") (pintype "passive"))
      (node (ref "R3") (pin "1") (pinfunction "1_1") (pintype "passive"))
    )
    (net (code "57") (name "Net-(IC6-SDA_B)") (class "Default")
      (node (ref "IC6") (pin "1") (pinfunction "SDA_B_1") (pintype "bidirectional"))
      (node (ref "J8") (pin "P$1") (pinfunction "1_P$1") (pintype "passive"))
      (node (ref "R4") (pin "2") (pinfunction "2_2") (pintype "passive"))
    )
    (net (code "58") (name "Net-(JP5-Pad1)") (class "Default")
      (node (ref "JP5") (pin "1") (pinfunction "1_1") (pintype "passive"))
      (node (ref "R12") (pin "2") (pinfunction "2_2") (pintype "passive"))
    )
    (net (code "59") (name "Net-(JP5-Pad3)") (class "Default")
      (node (ref "JP5") (pin "3") (pinfunction "3_3") (pintype "passive"))
      (node (ref "R11") (pin "2") (pinfunction "2_2") (pintype "passive"))
    )
    (net (code "60") (name "Net-(LED1-PadA)") (class "Default")
      (node (ref "LED1") (pin "A") (pinfunction "A_A") (pintype "passive"))
      (node (ref "R34") (pin "1") (pinfunction "1_1") (pintype "passive"))
    )
    (net (code "61") (name "Net-(LED3-PadA)") (class "Default")
      (node (ref "LED3") (pin "A") (pinfunction "A_A") (pintype "passive"))
      (node (ref "R33") (pin "1") (pinfunction "1_1") (pintype "passive"))
    )
    (net (code "62") (name "Net-(Q1-D)") (class "Default")
      (node (ref "C49") (pin "2") (pinfunction "2_2") (pintype "passive"))
      (node (ref "D2") (pin "+") (pinfunction "+_+") (pintype "passive"))
      (node (ref "L1") (pin "1") (pinfunction "1_1") (pintype "passive"))
      (node (ref "Q1") (pin "3") (pinfunction "D_3") (pintype "passive"))
    )
    (net (code "63") (name "Net-(Q1-G)") (class "Default")
      (node (ref "J9") (pin "2") (pinfunction "2_2") (pintype "bidirectional"))
      (node (ref "Q1") (pin "1") (pinfunction "G_1") (pintype "passive"))
      (node (ref "R6") (pin "1") (pinfunction "1_1") (pintype "passive"))
    )
    (net (code "64") (name "Net-(Q1-S)") (class "Default")
      (node (ref "J9") (pin "3") (pinfunction "3_3") (pintype "bidirectional"))
      (node (ref "Q1") (pin "2") (pinfunction "S_2") (pintype "passive"))
      (node (ref "R5") (pin "1") (pinfunction "1_1") (pintype "passive"))
    )
    (net (code "65") (name "Net-(U1-EXTINT)") (class "Default")
      (node (ref "R28") (pin "1") (pinfunction "1_1") (pintype "passive"))
      (node (ref "U1") (pin "5") (pinfunction "EXTINT_5") (pintype "bidirectional"))
    )
    (net (code "66") (name "Net-(U1-RF_IN)") (class "Default")
      (node (ref "ANT1") (pin "3") (pinfunction "3_3") (pintype "bidirectional"))
      (node (ref "D10") (pin "1") (pinfunction "1_1") (pintype "bidirectional"))
      (node (ref "FB2") (pin "1") (pinfunction "1_1") (pintype "passive"))
      (node (ref "U1") (pin "11") (pinfunction "RF_IN_11") (pintype "bidirectional"))
    )
    (net (code "67") (name "Net-(U1-RX)") (class "Default")
      (node (ref "R18") (pin "1") (pinfunction "1_1") (pintype "passive"))
      (node (ref "U1") (pin "3") (pinfunction "RX_3") (pintype "bidirectional"))
    )
    (net (code "68") (name "Net-(U1-SCL)") (class "Default")
      (node (ref "R26") (pin "1") (pinfunction "1_1") (pintype "passive"))
      (node (ref "U1") (pin "17") (pinfunction "SCL_17") (pintype "bidirectional"))
    )
    (net (code "69") (name "Net-(U1-SDA)") (class "Default")
      (node (ref "R19") (pin "1") (pinfunction "1_1") (pintype "passive"))
      (node (ref "U1") (pin "16") (pinfunction "SDA_16") (pintype "bidirectional"))
    )
    (net (code "70") (name "Net-(U1-TIMEPULSE)") (class "Default")
      (node (ref "R29") (pin "1") (pinfunction "1_1") (pintype "passive"))
      (node (ref "U1") (pin "4") (pinfunction "TIMEPULSE_4") (pintype "bidirectional"))
    )
    (net (code "71") (name "Net-(U1-TX)") (class "Default")
      (node (ref "R17") (pin "1") (pinfunction "1_1") (pintype "passive"))
      (node (ref "U1") (pin "2") (pinfunction "TX_2") (pintype "bidirectional"))
    )
    (net (code "72") (name "Net-(U1-VCC_RF)") (class "Default")
      (node (ref "R31") (pin "1") (pinfunction "1_1") (pintype "passive"))
      (node (ref "U1") (pin "14") (pinfunction "VCC_RF_14") (pintype "bidirectional"))
    )
    (net (code "73") (name "Net-(U1-~{RESET})") (class "Default")
      (node (ref "R10") (pin "1") (pinfunction "1_1") (pintype "passive"))
      (node (ref "U1") (pin "9") (pinfunction "~{RESET}_9") (pintype "bidirectional"))
    )
    (net (code "74") (name "Net-(U1-~{SAFEBOOT})") (class "Default")
      (node (ref "R30") (pin "1") (pinfunction "1_1") (pintype "passive"))
      (node (ref "U1") (pin "18") (pinfunction "~{SAFEBOOT}_18") (pintype "bidirectional"))
    )
    (net (code "75") (name "PPS") (class "Default")
      (node (ref "R29") (pin "2") (pinfunction "2_2") (pintype "passive"))
      (node (ref "R33") (pin "2") (pinfunction "2_2") (pintype "passive"))
    )
    (net (code "76") (name "RXI") (class "Default")
      (node (ref "R18") (pin "2") (pinfunction "2_2") (pintype "passive"))
    )
    (net (code "77") (name "SCK") (class "Default")
      (node (ref "J9") (pin "13") (pinfunction "13_13") (pintype "bidirectional"))
      (node (ref "SV2") (pin "3") (pinfunction "3_3") (pintype "passive"))
    )
    (net (code "78") (name "SCL") (class "Default")
      (node (ref "R11") (pin "1") (pinfunction "1_1") (pintype "passive"))
      (node (ref "R26") (pin "2") (pinfunction "2_2") (pintype "passive"))
    )
    (net (code "79") (name "SDA") (class "Default")
      (node (ref "R12") (pin "1") (pinfunction "1_1") (pintype "passive"))
      (node (ref "R19") (pin "2") (pinfunction "2_2") (pintype "passive"))
    )
    (net (code "80") (name "TXO") (class "Default")
      (node (ref "R17") (pin "2") (pinfunction "2_2") (pintype "passive"))
    )
    (net (code "81") (name "V+1V8") (class "Default")
      (node (ref "C4") (pin "P$2") (pinfunction "2_P$2") (pintype "passive"))
      (node (ref "C47") (pin "P$2") (pinfunction "2_P$2") (pintype "passive"))
      (node (ref "C48") (pin "P$2") (pinfunction "2_P$2") (pintype "passive"))
      (node (ref "IC4") (pin "11") (pinfunction "VDD_11") (pintype "bidirectional"))
      (node (ref "IC5") (pin "5") (pinfunction "VOUT_5") (pintype "bidirectional"))
      (node (ref "IC6") (pin "7") (pinfunction "VCCB_7") (pintype "bidirectional"))
      (node (ref "SV6") (pin "2") (pinfunction "2_2") (pintype "passive"))
    )
    (net (code "82") (name "unconnected-(IC1-LDR_2-Pad7)") (class "Default")
      (node (ref "IC1") (pin "7") (pinfunction "LDR_2_7") (pintype "bidirectional"))
    )
    (net (code "83") (name "unconnected-(IC1-LED-K_1-Pad8)") (class "Default")
      (node (ref "IC1") (pin "8") (pinfunction "LED-K_1_8") (pintype "bidirectional"))
    )
    (net (code "84") (name "unconnected-(IC1-NC_1-Pad1)") (class "Default")
      (node (ref "IC1") (pin "1") (pinfunction "NC_1_1") (pintype "bidirectional"))
    )
    (net (code "85") (name "unconnected-(IC1-NC_2-Pad6)") (class "Default")
      (node (ref "IC1") (pin "6") (pinfunction "NC_2_6") (pintype "bidirectional"))
    )
    (net (code "86") (name "unconnected-(IC1-SPI_CLK-Pad5)") (class "Default")
      (node (ref "IC1") (pin "5") (pinfunction "SPI_CLK_5") (pintype "bidirectional"))
    )
    (net (code "87") (name "unconnected-(IC1-SPI_CSN-Pad16)") (class "Default")
      (node (ref "IC1") (pin "16") (pinfunction "SPI_CSN_16") (pintype "bidirectional"))
    )
    (net (code "88") (name "unconnected-(IC1-SPI_DATA-Pad4)") (class "Default")
      (node (ref "IC1") (pin "4") (pinfunction "SPI_DATA_4") (pintype "bidirectional"))
    )
    (net (code "89") (name "unconnected-(IC1-SPI_MCLK-Pad15)") (class "Default")
      (node (ref "IC1") (pin "15") (pinfunction "SPI_MCLK_15") (pintype "bidirectional"))
    )
    (net (code "90") (name "unconnected-(IC2-CLKOUT-Pad1)") (class "Default")
      (node (ref "IC2") (pin "1") (pinfunction "CLKOUT_1") (pintype "bidirectional"))
    )
    (net (code "91") (name "unconnected-(IC4-N.C._1-Pad1)") (class "Default")
      (node (ref "IC4") (pin "1") (pinfunction "N.C._1_1") (pintype "bidirectional"))
    )
    (net (code "92") (name "unconnected-(IC4-N.C._2-Pad5)") (class "Default")
      (node (ref "IC4") (pin "5") (pinfunction "N.C._2_5") (pintype "bidirectional"))
    )
    (net (code "93") (name "unconnected-(IC4-N.C._3-Pad6)") (class "Default")
      (node (ref "IC4") (pin "6") (pinfunction "N.C._3_6") (pintype "bidirectional"))
    )
    (net (code "94") (name "unconnected-(IC4-N.C._4-Pad7)") (class "Default")
      (node (ref "IC4") (pin "7") (pinfunction "N.C._4_7") (pintype "bidirectional"))
    )
    (net (code "95") (name "unconnected-(IC4-N.C._5-Pad8)") (class "Default")
      (node (ref "IC4") (pin "8") (pinfunction "N.C._5_8") (pintype "bidirectional"))
    )
    (net (code "96") (name "unconnected-(IC4-N.C._6-Pad14)") (class "Default")
      (node (ref "IC4") (pin "14") (pinfunction "N.C._6_14") (pintype "bidirectional"))
    )
    (net (code "97") (name "unconnected-(IC4-~{INT}-Pad13)") (class "Default")
      (node (ref "IC4") (pin "13") (pinfunction "~{INT}_13") (pintype "bidirectional"))
    )
    (net (code "98") (name "unconnected-(IC5-NC-Pad4)") (class "Default")
      (node (ref "IC5") (pin "4") (pinfunction "NC_4") (pintype "no_connect"))
    )
    (net (code "99") (name "unconnected-(IC5-~{SHUTDOWN}-Pad3)") (class "Default")
      (node (ref "IC5") (pin "3") (pinfunction "~{SHUTDOWN}_3") (pintype "bidirectional"))
    )
    (net (code "100") (name "unconnected-(J9-Pad1)") (class "Default")
      (node (ref "J9") (pin "1") (pinfunction "1_1") (pintype "bidirectional"))
    )
    (net (code "101") (name "unconnected-(J9-Pad6)") (class "Default")
      (node (ref "J9") (pin "6") (pinfunction "6_6") (pintype "bidirectional"))
    )
    (net (code "102") (name "unconnected-(U1-LNA_EN-Pad13)") (class "Default")
      (node (ref "U1") (pin "13") (pinfunction "LNA_EN_13") (pintype "bidirectional"))
    )
  )
)
